# BANK_0.net
KiCad netlist of a schematic drawn in Altium Designer
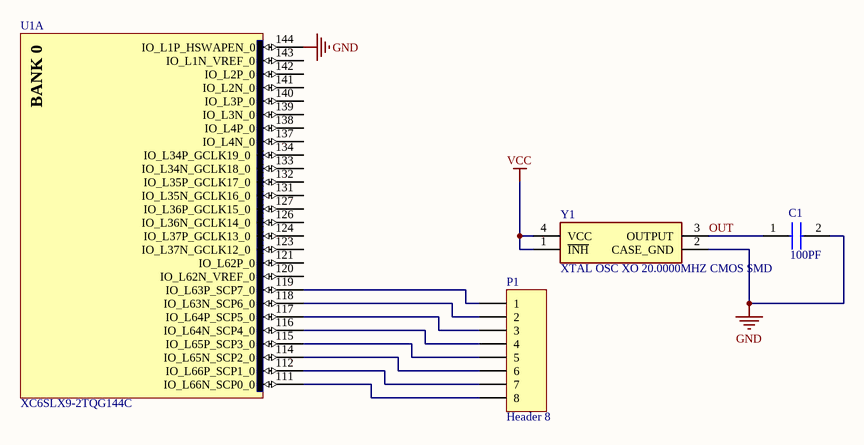
[diagram p0: BANK_0.SchDoc]

(export (version "E")
  (design (tool "Eeschema 10.0.6"))
  (components
    (comp (ref "C1")
      (value "100PF")
      (footprint "PcbLib1:CAPC2012X90N")
      (description "Capacitor")
      (fields
        (field (name "MANUFACTURER_PART_NUMBER") "885012207045")
        (field (name "MOUSER PART NUMBER") "710-885012207045")
      )
      (libsource (lib "Schlib1_FPGA") (part "CAP CER 0.1UF 16V X7R 0805"))
    )
    (comp (ref "P1")
      (value "Header 8")
      (footprint "HDR1X8")
      (description "Header, 8-Pin")
      (fields (field (name "PUBLISHER") "Altium Limited"))
      (libsource (lib "Schlib1_FPGA") (part "Header 8"))
    )
    (comp (ref "U1")
      (value "XC6SLX9-2TQG144C")
      (footprint "TQG144_N")
      (libsource (lib "Xilinx Spartan-6") (part "XC6SLX9-2TQG144C"))
    )
    (comp (ref "Y1")
      (value "XTAL OSC XO 20.0000MHZ CMOS SMD")
      (footprint "PcbLib1:KC5032A12.0000CM0E00")
      (description "Crystal or Oscillator")
      (fields
        (field (name "MANUFACTURER_PART_NUMBER") "KC5032A20.0000CMGE00")
        (field (name "MOUSER PART NUMBER") "581-KC5032A20.CMGE")
      )
      (libsource (lib "Schlib1_FPGA") (part "XTAL OSC XO 20.0000MHZ CMOS SMD"))
    )
  )
  (nets
    (net (code "1") (name "/OUT") (class "Default")
      (node (ref "C1") (pin "1") (pinfunction "1_1") (pintype "passive"))
      (node (ref "Y1") (pin "3") (pinfunction "OUTPUT_3") (pintype "passive"))
    )
    (net (code "2") (name "GND") (class "Default")
      (node (ref "C1") (pin "2") (pinfunction "2_2") (pintype "passive"))
      (node (ref "U1") (pin "144") (pinfunction "IO_L1P_HSWAPEN_0_144") (pintype "bidirectional"))
      (node (ref "Y1") (pin "2") (pinfunction "CASE_GND_2") (pintype "passive"))
    )
    (net (code "3") (name "Net-(U1A-IO_L63N_SCP6_0)") (class "Default")
      (node (ref "P1") (pin "2") (pinfunction "2_2") (pintype "passive"))
      (node (ref "U1") (pin "118") (pinfunction "IO_L63N_SCP6_0_118") (pintype "bidirectional"))
    )
    (net (code "4") (name "Net-(U1A-IO_L63P_SCP7_0)") (class "Default")
      (node (ref "P1") (pin "1") (pinfunction "1_1") (pintype "passive"))
      (node (ref "U1") (pin "119") (pinfunction "IO_L63P_SCP7_0_119") (pintype "bidirectional"))
    )
    (net (code "5") (name "Net-(U1A-IO_L64N_SCP4_0)") (class "Default")
      (node (ref "P1") (pin "4") (pinfunction "4_4") (pintype "passive"))
      (node (ref "U1") (pin "116") (pinfunction "IO_L64N_SCP4_0_116") (pintype "bidirectional"))
    )
    (net (code "6") (name "Net-(U1A-IO_L64P_SCP5_0)") (class "Default")
      (node (ref "P1") (pin "3") (pinfunction "3_3") (pintype "passive"))
      (node (ref "U1") (pin "117") (pinfunction "IO_L64P_SCP5_0_117") (pintype "bidirectional"))
    )
    (net (code "7") (name "Net-(U1A-IO_L65N_SCP2_0)") (class "Default")
      (node (ref "P1") (pin "6") (pinfunction "6_6") (pintype "passive"))
      (node (ref "U1") (pin "114") (pinfunction "IO_L65N_SCP2_0_114") (pintype "bidirectional"))
    )
    (net (code "8") (name "Net-(U1A-IO_L65P_SCP3_0)") (class "Default")
      (node (ref "P1") (pin "5") (pinfunction "5_5") (pintype "passive"))
      (node (ref "U1") (pin "115") (pinfunction "IO_L65P_SCP3_0_115") (pintype "bidirectional"))
    )
    (net (code "9") (name "Net-(U1A-IO_L66N_SCP0_0)") (class "Default")
      (node (ref "P1") (pin "8") (pinfunction "8_8") (pintype "passive"))
      (node (ref "U1") (pin "111") (pinfunction "IO_L66N_SCP0_0_111") (pintype "bidirectional"))
    )
    (net (code "10") (name "Net-(U1A-IO_L66P_SCP1_0)") (class "Default")
      (node (ref "P1") (pin "7") (pinfunction "7_7") (pintype "passive"))
      (node (ref "U1") (pin "112") (pinfunction "IO_L66P_SCP1_0_112") (pintype "bidirectional"))
    )
    (net (code "11") (name "VCC") (class "Default")
      (node (ref "Y1") (pin "1") (pinfunction "~{INH}_1") (pintype "passive"))
      (node (ref "Y1") (pin "4") (pinfunction "VCC_4") (pintype "passive"))
    )
    (net (code "12") (name "unconnected-(U1A-IO_L1N_VREF_0-Pad143)") (class "Default")
      (node (ref "U1") (pin "143") (pinfunction "IO_L1N_VREF_0_143") (pintype "bidirectional"))
    )
    (net (code "13") (name "unconnected-(U1A-IO_L2N_0-Pad141)") (class "Default")
      (node (ref "U1") (pin "141") (pinfunction "IO_L2N_0_141") (pintype "bidirectional"))
    )
    (net (code "14") (name "unconnected-(U1A-IO_L2P_0-Pad142)") (class "Default")
      (node (ref "U1") (pin "142") (pinfunction "IO_L2P_0_142") (pintype "bidirectional"))
    )
    (net (code "15") (name "unconnected-(U1A-IO_L3N_0-Pad139)") (class "Default")
      (node (ref "U1") (pin "139") (pinfunction "IO_L3N_0_139") (pintype "bidirectional"))
    )
    (net (code "16") (name "unconnected-(U1A-IO_L3P_0-Pad140)") (class "Default")
      (node (ref "U1") (pin "140") (pinfunction "IO_L3P_0_140") (pintype "bidirectional"))
    )
    (net (code "17") (name "unconnected-(U1A-IO_L4N_0-Pad137)") (class "Default")
      (node (ref "U1") (pin "137") (pinfunction "IO_L4N_0_137") (pintype "bidirectional"))
    )
    (net (code "18") (name "unconnected-(U1A-IO_L4P_0-Pad138)") (class "Default")
      (node (ref "U1") (pin "138") (pinfunction "IO_L4P_0_138") (pintype "bidirectional"))
    )
    (net (code "19") (name "unconnected-(U1A-IO_L34N_GCLK18_0-Pad133)") (class "Default")
      (node (ref "U1") (pin "133") (pinfunction "IO_L34N_GCLK18_0_133") (pintype "bidirectional"))
    )
    (net (code "20") (name "unconnected-(U1A-IO_L34P_GCLK19_0-Pad134)") (class "Default")
      (node (ref "U1") (pin "134") (pinfunction "IO_L34P_GCLK19_0_134") (pintype "bidirectional"))
    )
    (net (code "21") (name "unconnected-(U1A-IO_L35N_GCLK16_0-Pad131)") (class "Default")
      (node (ref "U1") (pin "131") (pinfunction "IO_L35N_GCLK16_0_131") (pintype "bidirectional"))
    )
    (net (code "22") (name "unconnected-(U1A-IO_L35P_GCLK17_0-Pad132)") (class "Default")
      (node (ref "U1") (pin "132") (pinfunction "IO_L35P_GCLK17_0_132") (pintype "bidirectional"))
    )
    (net (code "23") (name "unconnected-(U1A-IO_L36N_GCLK14_0-Pad126)") (class "Default")
      (node (ref "U1") (pin "126") (pinfunction "IO_L36N_GCLK14_0_126") (pintype "bidirectional"))
    )
    (net (code "24") (name "unconnected-(U1A-IO_L36P_GCLK15_0-Pad127)") (class "Default")
      (node (ref "U1") (pin "127") (pinfunction "IO_L36P_GCLK15_0_127") (pintype "bidirectional"))
    )
    (net (code "25") (name "unconnected-(U1A-IO_L37N_GCLK12_0-Pad123)") (class "Default")
      (node (ref "U1") (pin "123") (pinfunction "IO_L37N_GCLK12_0_123") (pintype "bidirectional"))
    )
    (net (code "26") (name "unconnected-(U1A-IO_L37P_GCLK13_0-Pad124)") (class "Default")
      (node (ref "U1") (pin "124") (pinfunction "IO_L37P_GCLK13_0_124") (pintype "bidirectional"))
    )
    (net (code "27") (name "unconnected-(U1A-IO_L62N_VREF_0-Pad120)") (class "Default")
      (node (ref "U1") (pin "120") (pinfunction "IO_L62N_VREF_0_120") (pintype "bidirectional"))
    )
    (net (code "28") (name "unconnected-(U1A-IO_L62P_0-Pad121)") (class "Default")
      (node (ref "U1") (pin "121") (pinfunction "IO_L62P_0_121") (pintype "bidirectional"))
    )
  )
)
